# DDR3A.net
KiCad netlist of a schematic drawn in Altium Designer
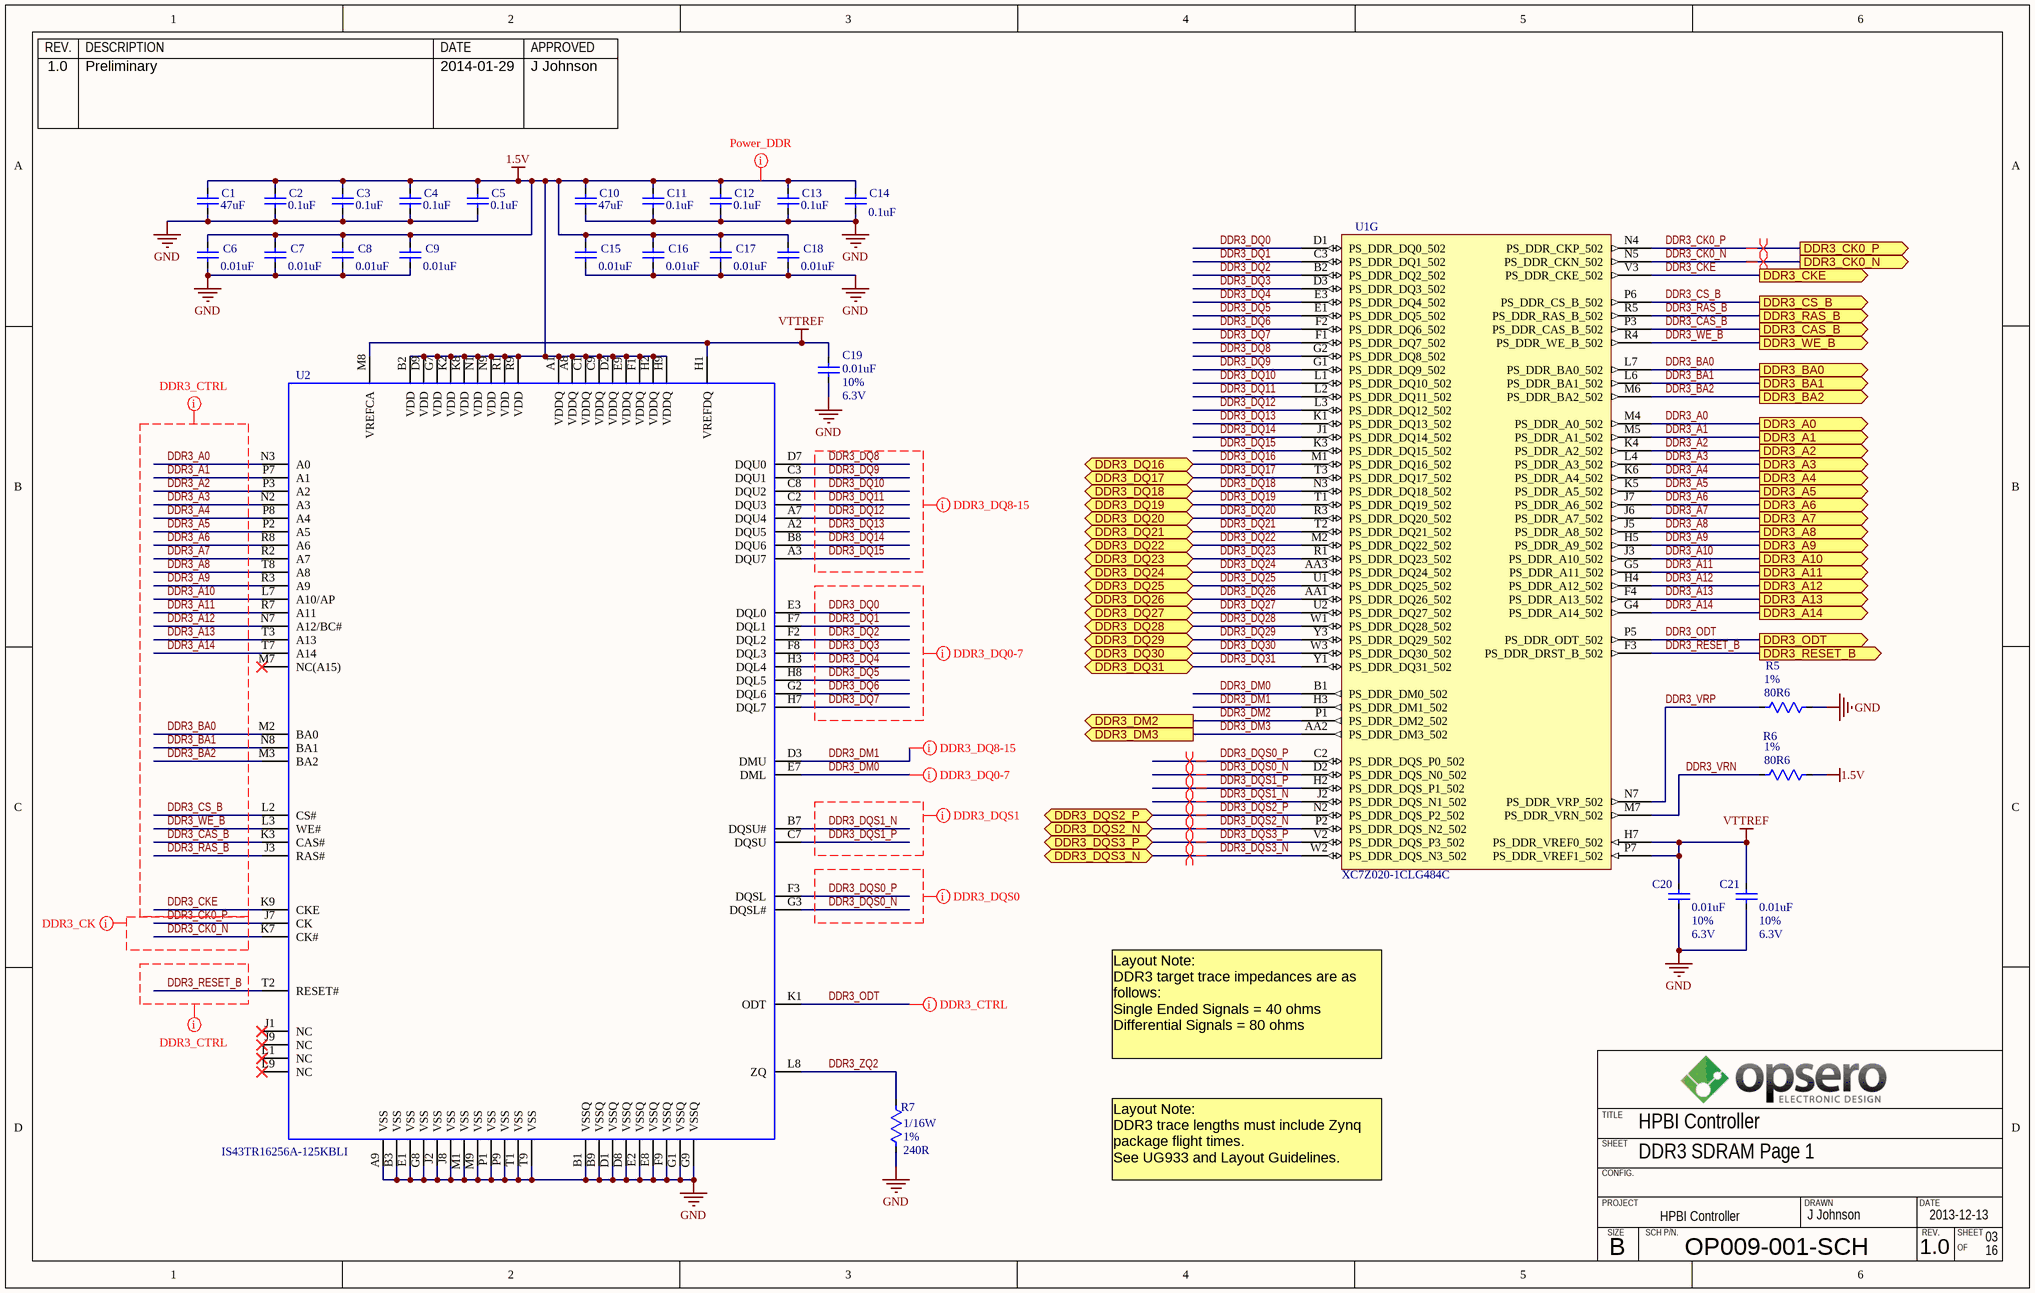
[diagram p0: DDR3A.SchDoc]

(export (version "E")
  (design (tool "Eeschema 10.0.6"))
  (components
    (comp (ref "C1")
      (value "47uF")
      (footprint "CAPC2013X125N")
      (description "Capacitor ceramic, X5R, 47uF, 6.3V, 20%, -55 to +85 C,")
      (fields (field (name "TOLERANCE") "20%") (field (name "VOLTAGE") "6.3V"))
      (libsource (lib "parts") (part "CAPACITOR_NP_TYPE1"))
    )
    (comp (ref "C2")
      (value "0.1uF")
      (footprint "CAPC0603X33N")
      (description "Capacitor ceramic, X5R, 0.1uF, 6.3V, 10%, -55 to +125 C, EIA0201")
      (fields (field (name "TOLERANCE") "10%") (field (name "VOLTAGE") "6.3V"))
      (libsource (lib "parts") (part "CAPACITOR_NP_TYPE1"))
    )
    (comp (ref "C3")
      (value "0.1uF")
      (footprint "CAPC0603X33N")
      (description "Capacitor ceramic, X5R, 0.1uF, 6.3V, 10%, -55 to +125 C, EIA0201")
      (fields (field (name "TOLERANCE") "10%") (field (name "VOLTAGE") "6.3V"))
      (libsource (lib "parts") (part "CAPACITOR_NP_TYPE1"))
    )
    (comp (ref "C4")
      (value "0.1uF")
      (footprint "CAPC0603X33N")
      (description "Capacitor ceramic, X5R, 0.1uF, 6.3V, 10%, -55 to +125 C, EIA0201")
      (fields (field (name "TOLERANCE") "10%") (field (name "VOLTAGE") "6.3V"))
      (libsource (lib "parts") (part "CAPACITOR_NP_TYPE1"))
    )
    (comp (ref "C5")
      (value "0.1uF")
      (footprint "CAPC0603X33N")
      (description "Capacitor ceramic, X5R, 0.1uF, 6.3V, 10%, -55 to +125 C, EIA0201")
      (fields (field (name "TOLERANCE") "10%") (field (name "VOLTAGE") "6.3V"))
      (libsource (lib "parts") (part "CAPACITOR_NP_TYPE1"))
    )
    (comp (ref "C6")
      (value "0.01uF")
      (footprint "CAPC0603X33N")
      (description "Capacitor ceramic, X5R, 0.01uF, 6.3V, 10%, -55 to +125 C, EIA0201")
      (fields (field (name "TOLERANCE") "10%") (field (name "VOLTAGE") "6.3V"))
      (libsource (lib "parts") (part "CAPACITOR_NP_TYPE1"))
    )
    (comp (ref "C7")
      (value "0.01uF")
      (footprint "CAPC0603X33N")
      (description "Capacitor ceramic, X5R, 0.01uF, 6.3V, 10%, -55 to +125 C, EIA0201")
      (fields (field (name "TOLERANCE") "10%") (field (name "VOLTAGE") "6.3V"))
      (libsource (lib "parts") (part "CAPACITOR_NP_TYPE1"))
    )
    (comp (ref "C8")
      (value "0.01uF")
      (footprint "CAPC0603X33N")
      (description "Capacitor ceramic, X5R, 0.01uF, 6.3V, 10%, -55 to +125 C, EIA0201")
      (fields (field (name "TOLERANCE") "10%") (field (name "VOLTAGE") "6.3V"))
      (libsource (lib "parts") (part "CAPACITOR_NP_TYPE1"))
    )
    (comp (ref "C9")
      (value "0.01uF")
      (footprint "CAPC0603X33N")
      (description "Capacitor ceramic, X5R, 0.01uF, 6.3V, 10%, -55 to +125 C, EIA0201")
      (fields (field (name "TOLERANCE") "10%") (field (name "VOLTAGE") "6.3V"))
      (libsource (lib "parts") (part "CAPACITOR_NP_TYPE1"))
    )
    (comp (ref "C10")
      (value "47uF")
      (footprint "CAPC2013X125N")
      (description "Capacitor ceramic, X5R, 47uF, 6.3V, 20%, -55 to +85 C,")
      (fields (field (name "TOLERANCE") "20%") (field (name "VOLTAGE") "6.3V"))
      (libsource (lib "parts") (part "CAPACITOR_NP_TYPE1"))
    )
    (comp (ref "C11")
      (value "0.1uF")
      (footprint "CAPC0603X33N")
      (description "Capacitor ceramic, X5R, 0.1uF, 6.3V, 10%, -55 to +125 C, EIA0201")
      (fields (field (name "TOLERANCE") "10%") (field (name "VOLTAGE") "6.3V"))
      (libsource (lib "parts") (part "CAPACITOR_NP_TYPE1"))
    )
    (comp (ref "C12")
      (value "0.1uF")
      (footprint "CAPC0603X33N")
      (description "Capacitor ceramic, X5R, 0.1uF, 6.3V, 10%, -55 to +125 C, EIA0201")
      (fields (field (name "TOLERANCE") "10%") (field (name "VOLTAGE") "6.3V"))
      (libsource (lib "parts") (part "CAPACITOR_NP_TYPE1"))
    )
    (comp (ref "C13")
      (value "0.1uF")
      (footprint "CAPC0603X33N")
      (description "Capacitor ceramic, X5R, 0.1uF, 6.3V, 10%, -55 to +125 C, EIA0201")
      (fields (field (name "TOLERANCE") "10%") (field (name "VOLTAGE") "6.3V"))
      (libsource (lib "parts") (part "CAPACITOR_NP_TYPE1"))
    )
    (comp (ref "C14")
      (value "0.1uF")
      (footprint "CAPC0603X33N")
      (description "Capacitor ceramic, X5R, 0.1uF, 6.3V, 10%, -55 to +125 C, EIA0201")
      (fields (field (name "TOLERANCE") "10%") (field (name "VOLTAGE") "6.3V"))
      (libsource (lib "parts") (part "CAPACITOR_NP_TYPE1"))
    )
    (comp (ref "C15")
      (value "0.01uF")
      (footprint "CAPC0603X33N")
      (description "Capacitor ceramic, X5R, 0.01uF, 6.3V, 10%, -55 to +125 C, EIA0201")
      (fields (field (name "TOLERANCE") "10%") (field (name "VOLTAGE") "6.3V"))
      (libsource (lib "parts") (part "CAPACITOR_NP_TYPE1"))
    )
    (comp (ref "C16")
      (value "0.01uF")
      (footprint "CAPC0603X33N")
      (description "Capacitor ceramic, X5R, 0.01uF, 6.3V, 10%, -55 to +125 C, EIA0201")
      (fields (field (name "TOLERANCE") "10%") (field (name "VOLTAGE") "6.3V"))
      (libsource (lib "parts") (part "CAPACITOR_NP_TYPE1"))
    )
    (comp (ref "C17")
      (value "0.01uF")
      (footprint "CAPC0603X33N")
      (description "Capacitor ceramic, X5R, 0.01uF, 6.3V, 10%, -55 to +125 C, EIA0201")
      (fields (field (name "TOLERANCE") "10%") (field (name "VOLTAGE") "6.3V"))
      (libsource (lib "parts") (part "CAPACITOR_NP_TYPE1"))
    )
    (comp (ref "C18")
      (value "0.01uF")
      (footprint "CAPC0603X33N")
      (description "Capacitor ceramic, X5R, 0.01uF, 6.3V, 10%, -55 to +125 C, EIA0201")
      (fields (field (name "TOLERANCE") "10%") (field (name "VOLTAGE") "6.3V"))
      (libsource (lib "parts") (part "CAPACITOR_NP_TYPE1"))
    )
    (comp (ref "C19")
      (value "0.01uF")
      (footprint "CAPC0603X33N")
      (description "Capacitor ceramic, X5R, 0.01uF, 6.3V, 10%, -55 to +125 C, EIA0201")
      (fields
        (field (name "TOLERANCE") "10%")
        (field (name "VOLTAGE") "6.3V")
        (field (name "Comment") "CAPACITOR_NP_TYPE1")
      )
      (libsource (lib "parts") (part "CAPACITOR_NP_TYPE1"))
    )
    (comp (ref "C20")
      (value "0.01uF")
      (footprint "CAPC0603X33N")
      (description "Capacitor ceramic, X5R, 0.01uF, 6.3V, 10%, -55 to +125 C, EIA0201")
      (fields
        (field (name "TOLERANCE") "10%")
        (field (name "VOLTAGE") "6.3V")
        (field (name "Comment") "CAPACITOR_NP_TYPE1")
      )
      (libsource (lib "parts") (part "CAPACITOR_NP_TYPE1"))
    )
    (comp (ref "C21")
      (value "0.01uF")
      (footprint "CAPC0603X33N")
      (description "Capacitor ceramic, X5R, 0.01uF, 6.3V, 10%, -55 to +125 C, EIA0201")
      (fields
        (field (name "TOLERANCE") "10%")
        (field (name "VOLTAGE") "6.3V")
        (field (name "Comment") "CAPACITOR_NP_TYPE1")
      )
      (libsource (lib "parts") (part "CAPACITOR_NP_TYPE1"))
    )
    (comp (ref "R5")
      (value "80R6")
      (footprint "RESC1005X33N")
      (description "Resistor, 80R6, 1/16W, 1%, -50 to +155 C, EIA0402, EIA(M)1005")
      (fields (field (name "VOLTAGE") "50V") (field (name "POWER") "1/16W") (field (name "TOLERANCE") "1%"))
      (libsource (lib "parts") (part "RESISTOR_TYPE1"))
    )
    (comp (ref "R6")
      (value "80R6")
      (footprint "RESC1005X33N")
      (description "Resistor, 80R6, 1/16W, 1%, -50 to +155 C, EIA0402, EIA(M)1005")
      (fields (field (name "VOLTAGE") "50V") (field (name "POWER") "1/16W") (field (name "TOLERANCE") "1%"))
      (libsource (lib "parts") (part "RESISTOR_TYPE1"))
    )
    (comp (ref "R7")
      (value "240R")
      (footprint "RESC1005X33N")
      (description "Resistor, 240R, 1/16W, 1%, -50 to +155 C, EIA0402, EIA(M)1005")
      (fields (field (name "VOLTAGE") "50V") (field (name "POWER") "1/16W") (field (name "TOLERANCE") "1%"))
      (libsource (lib "parts") (part "RESISTOR_TYPE1"))
    )
    (comp (ref "U1")
      (value "XC7Z020-1CLG484C")
      (footprint "CLG484")
      (description "667 MHz Zynq™-7000 AP SoC, 130 PS I/O, 200 FPGA I/O, 484-Ball BGA, Speed Grade 1, Commercial Grade")
      (fields (field (name "GENERIC PART NUMBER") "XC7Z020") (field (name "MANUFACTURER") "Xilinx"))
      (libsource (lib "parts") (part "XC7Z020-1CLG484C"))
    )
    (comp (ref "U2")
      (value "IS43TR16256A-125KBLI")
      (footprint "BGA96C80P6X16_900X1300X120")
      (libsource (lib "parts") (part "IS43TR16256A-125KBLI"))
    )
  )
  (nets
    (net (code "1") (name "/DDR3_A0") (class "Default")
      (node (ref "U1") (pin "M4") (pinfunction "PS_DDR_A0_502_M4") (pintype "output"))
      (node (ref "U2") (pin "N3") (pinfunction "A0_N3") (pintype "passive"))
    )
    (net (code "2") (name "/DDR3_A1") (class "Default")
      (node (ref "U1") (pin "M5") (pinfunction "PS_DDR_A1_502_M5") (pintype "output"))
      (node (ref "U2") (pin "P7") (pinfunction "A1_P7") (pintype "passive"))
    )
    (net (code "3") (name "/DDR3_A2") (class "Default")
      (node (ref "U1") (pin "K4") (pinfunction "PS_DDR_A2_502_K4") (pintype "output"))
      (node (ref "U2") (pin "P3") (pinfunction "A2_P3") (pintype "passive"))
    )
    (net (code "4") (name "/DDR3_A3") (class "Default")
      (node (ref "U1") (pin "L4") (pinfunction "PS_DDR_A3_502_L4") (pintype "output"))
      (node (ref "U2") (pin "N2") (pinfunction "A3_N2") (pintype "passive"))
    )
    (net (code "5") (name "/DDR3_A4") (class "Default")
      (node (ref "U1") (pin "K6") (pinfunction "PS_DDR_A4_502_K6") (pintype "output"))
      (node (ref "U2") (pin "P8") (pinfunction "A4_P8") (pintype "passive"))
    )
    (net (code "6") (name "/DDR3_A5") (class "Default")
      (node (ref "U1") (pin "K5") (pinfunction "PS_DDR_A5_502_K5") (pintype "output"))
      (node (ref "U2") (pin "P2") (pinfunction "A5_P2") (pintype "passive"))
    )
    (net (code "7") (name "/DDR3_A6") (class "Default")
      (node (ref "U1") (pin "J7") (pinfunction "PS_DDR_A6_502_J7") (pintype "output"))
      (node (ref "U2") (pin "R8") (pinfunction "A6_R8") (pintype "passive"))
    )
    (net (code "8") (name "/DDR3_A7") (class "Default")
      (node (ref "U1") (pin "J6") (pinfunction "PS_DDR_A7_502_J6") (pintype "output"))
      (node (ref "U2") (pin "R2") (pinfunction "A7_R2") (pintype "passive"))
    )
    (net (code "9") (name "/DDR3_A8") (class "Default")
      (node (ref "U1") (pin "J5") (pinfunction "PS_DDR_A8_502_J5") (pintype "output"))
      (node (ref "U2") (pin "T8") (pinfunction "A8_T8") (pintype "passive"))
    )
    (net (code "10") (name "/DDR3_A9") (class "Default")
      (node (ref "U1") (pin "H5") (pinfunction "PS_DDR_A9_502_H5") (pintype "output"))
      (node (ref "U2") (pin "R3") (pinfunction "A9_R3") (pintype "passive"))
    )
    (net (code "11") (name "/DDR3_A10") (class "Default")
      (node (ref "U1") (pin "J3") (pinfunction "PS_DDR_A10_502_J3") (pintype "output"))
      (node (ref "U2") (pin "L7") (pinfunction "A10/AP_L7") (pintype "passive"))
    )
    (net (code "12") (name "/DDR3_A11") (class "Default")
      (node (ref "U1") (pin "G5") (pinfunction "PS_DDR_A11_502_G5") (pintype "output"))
      (node (ref "U2") (pin "R7") (pinfunction "A11_R7") (pintype "passive"))
    )
    (net (code "13") (name "/DDR3_A12") (class "Default")
      (node (ref "U1") (pin "H4") (pinfunction "PS_DDR_A12_502_H4") (pintype "output"))
      (node (ref "U2") (pin "N7") (pinfunction "A12/BC#_N7") (pintype "passive"))
    )
    (net (code "14") (name "/DDR3_A13") (class "Default")
      (node (ref "U1") (pin "F4") (pinfunction "PS_DDR_A13_502_F4") (pintype "output"))
      (node (ref "U2") (pin "T3") (pinfunction "A13_T3") (pintype "passive"))
    )
    (net (code "15") (name "/DDR3_A14") (class "Default")
      (node (ref "U1") (pin "G4") (pinfunction "PS_DDR_A14_502_G4") (pintype "output"))
      (node (ref "U2") (pin "T7") (pinfunction "A14_T7") (pintype "passive"))
    )
    (net (code "16") (name "/DDR3_BA0") (class "Default")
      (node (ref "U1") (pin "L7") (pinfunction "PS_DDR_BA0_502_L7") (pintype "output"))
      (node (ref "U2") (pin "M2") (pinfunction "BA0_M2") (pintype "passive"))
    )
    (net (code "17") (name "/DDR3_BA1") (class "Default")
      (node (ref "U1") (pin "L6") (pinfunction "PS_DDR_BA1_502_L6") (pintype "output"))
      (node (ref "U2") (pin "N8") (pinfunction "BA1_N8") (pintype "passive"))
    )
    (net (code "18") (name "/DDR3_BA2") (class "Default")
      (node (ref "U1") (pin "M6") (pinfunction "PS_DDR_BA2_502_M6") (pintype "output"))
      (node (ref "U2") (pin "M3") (pinfunction "BA2_M3") (pintype "passive"))
    )
    (net (code "19") (name "/DDR3_CAS_B") (class "Default")
      (node (ref "U1") (pin "P3") (pinfunction "PS_DDR_CAS_B_502_P3") (pintype "output"))
      (node (ref "U2") (pin "K3") (pinfunction "CAS#_K3") (pintype "passive"))
    )
    (net (code "20") (name "/DDR3_CK0_N") (class "Default")
      (node (ref "U1") (pin "N5") (pinfunction "PS_DDR_CKN_502_N5") (pintype "output"))
      (node (ref "U2") (pin "K7") (pinfunction "CK#_K7") (pintype "passive"))
    )
    (net (code "21") (name "/DDR3_CK0_P") (class "Default")
      (node (ref "U1") (pin "N4") (pinfunction "PS_DDR_CKP_502_N4") (pintype "output"))
      (node (ref "U2") (pin "J7") (pinfunction "CK_J7") (pintype "passive"))
    )
    (net (code "22") (name "/DDR3_CKE") (class "Default")
      (node (ref "U1") (pin "V3") (pinfunction "PS_DDR_CKE_502_V3") (pintype "output"))
      (node (ref "U2") (pin "K9") (pinfunction "CKE_K9") (pintype "passive"))
    )
    (net (code "23") (name "/DDR3_CS_B") (class "Default")
      (node (ref "U1") (pin "P6") (pinfunction "PS_DDR_CS_B_502_P6") (pintype "output"))
      (node (ref "U2") (pin "L2") (pinfunction "CS#_L2") (pintype "passive"))
    )
    (net (code "24") (name "/DDR3_DM0") (class "Default")
      (node (ref "U1") (pin "B1") (pinfunction "PS_DDR_DM0_502_B1") (pintype "output"))
      (node (ref "U2") (pin "E7") (pinfunction "DML_E7") (pintype "passive"))
    )
    (net (code "25") (name "/DDR3_DM1") (class "Default")
      (node (ref "U1") (pin "H3") (pinfunction "PS_DDR_DM1_502_H3") (pintype "output"))
      (node (ref "U2") (pin "D3") (pinfunction "DMU_D3") (pintype "passive"))
    )
    (net (code "26") (name "/DDR3_DM2") (class "Default")
      (node (ref "U1") (pin "P1") (pinfunction "PS_DDR_DM2_502_P1") (pintype "output"))
    )
    (net (code "27") (name "/DDR3_DM3") (class "Default")
      (node (ref "U1") (pin "AA2") (pinfunction "PS_DDR_DM3_502_AA2") (pintype "output"))
    )
    (net (code "28") (name "/DDR3_DQ0") (class "Default")
      (node (ref "U1") (pin "D1") (pinfunction "PS_DDR_DQ0_502_D1") (pintype "bidirectional"))
      (node (ref "U2") (pin "E3") (pinfunction "DQL0_E3") (pintype "passive"))
    )
    (net (code "29") (name "/DDR3_DQ1") (class "Default")
      (node (ref "U1") (pin "C3") (pinfunction "PS_DDR_DQ1_502_C3") (pintype "bidirectional"))
      (node (ref "U2") (pin "F7") (pinfunction "DQL1_F7") (pintype "passive"))
    )
    (net (code "30") (name "/DDR3_DQ2") (class "Default")
      (node (ref "U1") (pin "B2") (pinfunction "PS_DDR_DQ2_502_B2") (pintype "bidirectional"))
      (node (ref "U2") (pin "F2") (pinfunction "DQL2_F2") (pintype "passive"))
    )
    (net (code "31") (name "/DDR3_DQ3") (class "Default")
      (node (ref "U1") (pin "D3") (pinfunction "PS_DDR_DQ3_502_D3") (pintype "bidirectional"))
      (node (ref "U2") (pin "F8") (pinfunction "DQL3_F8") (pintype "passive"))
    )
    (net (code "32") (name "/DDR3_DQ4") (class "Default")
      (node (ref "U1") (pin "E3") (pinfunction "PS_DDR_DQ4_502_E3") (pintype "bidirectional"))
      (node (ref "U2") (pin "H3") (pinfunction "DQL4_H3") (pintype "passive"))
    )
    (net (code "33") (name "/DDR3_DQ5") (class "Default")
      (node (ref "U1") (pin "E1") (pinfunction "PS_DDR_DQ5_502_E1") (pintype "bidirectional"))
      (node (ref "U2") (pin "H8") (pinfunction "DQL5_H8") (pintype "passive"))
    )
    (net (code "34") (name "/DDR3_DQ6") (class "Default")
      (node (ref "U1") (pin "F2") (pinfunction "PS_DDR_DQ6_502_F2") (pintype "bidirectional"))
      (node (ref "U2") (pin "G2") (pinfunction "DQL6_G2") (pintype "passive"))
    )
    (net (code "35") (name "/DDR3_DQ7") (class "Default")
      (node (ref "U1") (pin "F1") (pinfunction "PS_DDR_DQ7_502_F1") (pintype "bidirectional"))
      (node (ref "U2") (pin "H7") (pinfunction "DQL7_H7") (pintype "passive"))
    )
    (net (code "36") (name "/DDR3_DQ8") (class "Default")
      (node (ref "U1") (pin "G2") (pinfunction "PS_DDR_DQ8_502_G2") (pintype "bidirectional"))
      (node (ref "U2") (pin "D7") (pinfunction "DQU0_D7") (pintype "passive"))
    )
    (net (code "37") (name "/DDR3_DQ9") (class "Default")
      (node (ref "U1") (pin "G1") (pinfunction "PS_DDR_DQ9_502_G1") (pintype "bidirectional"))
      (node (ref "U2") (pin "C3") (pinfunction "DQU1_C3") (pintype "passive"))
    )
    (net (code "38") (name "/DDR3_DQ10") (class "Default")
      (node (ref "U1") (pin "L1") (pinfunction "PS_DDR_DQ10_502_L1") (pintype "bidirectional"))
      (node (ref "U2") (pin "C8") (pinfunction "DQU2_C8") (pintype "passive"))
    )
    (net (code "39") (name "/DDR3_DQ11") (class "Default")
      (node (ref "U1") (pin "L2") (pinfunction "PS_DDR_DQ11_502_L2") (pintype "bidirectional"))
      (node (ref "U2") (pin "C2") (pinfunction "DQU3_C2") (pintype "passive"))
    )
    (net (code "40") (name "/DDR3_DQ12") (class "Default")
      (node (ref "U1") (pin "L3") (pinfunction "PS_DDR_DQ12_502_L3") (pintype "bidirectional"))
      (node (ref "U2") (pin "A7") (pinfunction "DQU4_A7") (pintype "passive"))
    )
    (net (code "41") (name "/DDR3_DQ13") (class "Default")
      (node (ref "U1") (pin "K1") (pinfunction "PS_DDR_DQ13_502_K1") (pintype "bidirectional"))
      (node (ref "U2") (pin "A2") (pinfunction "DQU5_A2") (pintype "passive"))
    )
    (net (code "42") (name "/DDR3_DQ14") (class "Default")
      (node (ref "U1") (pin "J1") (pinfunction "PS_DDR_DQ14_502_J1") (pintype "bidirectional"))
      (node (ref "U2") (pin "B8") (pinfunction "DQU6_B8") (pintype "passive"))
    )
    (net (code "43") (name "/DDR3_DQ15") (class "Default")
      (node (ref "U1") (pin "K3") (pinfunction "PS_DDR_DQ15_502_K3") (pintype "bidirectional"))
      (node (ref "U2") (pin "A3") (pinfunction "DQU7_A3") (pintype "passive"))
    )
    (net (code "44") (name "/DDR3_DQ16") (class "Default")
      (node (ref "U1") (pin "M1") (pinfunction "PS_DDR_DQ16_502_M1") (pintype "bidirectional"))
    )
    (net (code "45") (name "/DDR3_DQ17") (class "Default")
      (node (ref "U1") (pin "T3") (pinfunction "PS_DDR_DQ17_502_T3") (pintype "bidirectional"))
    )
    (net (code "46") (name "/DDR3_DQ18") (class "Default")
      (node (ref "U1") (pin "N3") (pinfunction "PS_DDR_DQ18_502_N3") (pintype "bidirectional"))
    )
    (net (code "47") (name "/DDR3_DQ19") (class "Default")
      (node (ref "U1") (pin "T1") (pinfunction "PS_DDR_DQ19_502_T1") (pintype "bidirectional"))
    )
    (net (code "48") (name "/DDR3_DQ20") (class "Default")
      (node (ref "U1") (pin "R3") (pinfunction "PS_DDR_DQ20_502_R3") (pintype "bidirectional"))
    )
    (net (code "49") (name "/DDR3_DQ21") (class "Default")
      (node (ref "U1") (pin "T2") (pinfunction "PS_DDR_DQ21_502_T2") (pintype "bidirectional"))
    )
    (net (code "50") (name "/DDR3_DQ22") (class "Default")
      (node (ref "U1") (pin "M2") (pinfunction "PS_DDR_DQ22_502_M2") (pintype "bidirectional"))
    )
    (net (code "51") (name "/DDR3_DQ23") (class "Default")
      (node (ref "U1") (pin "R1") (pinfunction "PS_DDR_DQ23_502_R1") (pintype "bidirectional"))
    )
    (net (code "52") (name "/DDR3_DQ24") (class "Default")
      (node (ref "U1") (pin "AA3") (pinfunction "PS_DDR_DQ24_502_AA3") (pintype "bidirectional"))
    )
    (net (code "53") (name "/DDR3_DQ25") (class "Default")
      (node (ref "U1") (pin "U1") (pinfunction "PS_DDR_DQ25_502_U1") (pintype "bidirectional"))
    )
    (net (code "54") (name "/DDR3_DQ26") (class "Default")
      (node (ref "U1") (pin "AA1") (pinfunction "PS_DDR_DQ26_502_AA1") (pintype "bidirectional"))
    )
    (net (code "55") (name "/DDR3_DQ27") (class "Default")
      (node (ref "U1") (pin "U2") (pinfunction "PS_DDR_DQ27_502_U2") (pintype "bidirectional"))
    )
    (net (code "56") (name "/DDR3_DQ28") (class "Default")
      (node (ref "U1") (pin "W1") (pinfunction "PS_DDR_DQ28_502_W1") (pintype "bidirectional"))
    )
    (net (code "57") (name "/DDR3_DQ29") (class "Default")
      (node (ref "U1") (pin "Y3") (pinfunction "PS_DDR_DQ29_502_Y3") (pintype "bidirectional"))
    )
    (net (code "58") (name "/DDR3_DQ30") (class "Default")
      (node (ref "U1") (pin "W3") (pinfunction "PS_DDR_DQ30_502_W3") (pintype "bidirectional"))
    )
    (net (code "59") (name "/DDR3_DQ31") (class "Default")
      (node (ref "U1") (pin "Y1") (pinfunction "PS_DDR_DQ31_502_Y1") (pintype "bidirectional"))
    )
    (net (code "60") (name "/DDR3_DQS0_N") (class "Default")
      (node (ref "U1") (pin "D2") (pinfunction "PS_DDR_DQS_N0_502_D2") (pintype "bidirectional"))
      (node (ref "U2") (pin "G3") (pinfunction "DQSL#_G3") (pintype "passive"))
    )
    (net (code "61") (name "/DDR3_DQS0_P") (class "Default")
      (node (ref "U1") (pin "C2") (pinfunction "PS_DDR_DQS_P0_502_C2") (pintype "bidirectional"))
      (node (ref "U2") (pin "F3") (pinfunction "DQSL_F3") (pintype "passive"))
    )
    (net (code "62") (name "/DDR3_DQS1_N") (class "Default")
      (node (ref "U1") (pin "J2") (pinfunction "PS_DDR_DQS_N1_502_J2") (pintype "bidirectional"))
      (node (ref "U2") (pin "B7") (pinfunction "DQSU#_B7") (pintype "passive"))
    )
    (net (code "63") (name "/DDR3_DQS1_P") (class "Default")
      (node (ref "U1") (pin "H2") (pinfunction "PS_DDR_DQS_P1_502_H2") (pintype "bidirectional"))
      (node (ref "U2") (pin "C7") (pinfunction "DQSU_C7") (pintype "passive"))
    )
    (net (code "64") (name "/DDR3_DQS2_N") (class "Default")
      (node (ref "U1") (pin "P2") (pinfunction "PS_DDR_DQS_N2_502_P2") (pintype "bidirectional"))
    )
    (net (code "65") (name "/DDR3_DQS2_P") (class "Default")
      (node (ref "U1") (pin "N2") (pinfunction "PS_DDR_DQS_P2_502_N2") (pintype "bidirectional"))
    )
    (net (code "66") (name "/DDR3_DQS3_N") (class "Default")
      (node (ref "U1") (pin "W2") (pinfunction "PS_DDR_DQS_N3_502_W2") (pintype "bidirectional"))
    )
    (net (code "67") (name "/DDR3_DQS3_P") (class "Default")
      (node (ref "U1") (pin "V2") (pinfunction "PS_DDR_DQS_P3_502_V2") (pintype "bidirectional"))
    )
    (net (code "68") (name "/DDR3_ODT") (class "Default")
      (node (ref "U1") (pin "P5") (pinfunction "PS_DDR_ODT_502_P5") (pintype "output"))
      (node (ref "U2") (pin "K1") (pinfunction "ODT_K1") (pintype "passive"))
    )
    (net (code "69") (name "/DDR3_RAS_B") (class "Default")
      (node (ref "U1") (pin "R5") (pinfunction "PS_DDR_RAS_B_502_R5") (pintype "output"))
      (node (ref "U2") (pin "J3") (pinfunction "RAS#_J3") (pintype "passive"))
    )
    (net (code "70") (name "/DDR3_RESET_B") (class "Default")
      (node (ref "U1") (pin "F3") (pinfunction "PS_DDR_DRST_B_502_F3") (pintype "output"))
      (node (ref "U2") (pin "T2") (pinfunction "RESET#_T2") (pintype "passive"))
    )
    (net (code "71") (name "/DDR3_VRN") (class "Default")
      (node (ref "R6") (pin "2") (pinfunction "2_2") (pintype "passive"))
      (node (ref "U1") (pin "M7") (pinfunction "PS_DDR_VRN_502_M7") (pintype "output"))
    )
    (net (code "72") (name "/DDR3_VRP") (class "Default")
      (node (ref "R5") (pin "1") (pinfunction "1_1") (pintype "passive"))
      (node (ref "U1") (pin "N7") (pinfunction "PS_DDR_VRP_502_N7") (pintype "output"))
    )
    (net (code "73") (name "/DDR3_WE_B") (class "Default")
      (node (ref "U1") (pin "R4") (pinfunction "PS_DDR_WE_B_502_R4") (pintype "output"))
      (node (ref "U2") (pin "L3") (pinfunction "WE#_L3") (pintype "passive"))
    )
    (net (code "74") (name "/DDR3_ZQ2") (class "Default")
      (node (ref "R7") (pin "2") (pinfunction "2_2") (pintype "passive"))
      (node (ref "U2") (pin "L8") (pinfunction "ZQ_L8") (pintype "passive"))
    )
    (net (code "75") (name "1.5V") (class "Default")
      (node (ref "C1") (pin "1") (pinfunction "1_1") (pintype "passive"))
      (node (ref "C10") (pin "1") (pinfunction "1_1") (pintype "passive"))
      (node (ref "C11") (pin "1") (pinfunction "1_1") (pintype "passive"))
      (node (ref "C12") (pin "1") (pinfunction "1_1") (pintype "passive"))
      (node (ref "C13") (pin "1") (pinfunction "1_1") (pintype "passive"))
      (node (ref "C14") (pin "1") (pinfunction "1_1") (pintype "passive"))
      (node (ref "C15") (pin "1") (pinfunction "1_1") (pintype "passive"))
      (node (ref "C16") (pin "1") (pinfunction "1_1") (pintype "passive"))
      (node (ref "C17") (pin "1") (pinfunction "1_1") (pintype "passive"))
      (node (ref "C18") (pin "1") (pinfunction "1_1") (pintype "passive"))
      (node (ref "C2") (pin "1") (pinfunction "1_1") (pintype "passive"))
      (node (ref "C3") (pin "1") (pinfunction "1_1") (pintype "passive"))
      (node (ref "C4") (pin "1") (pinfunction "1_1") (pintype "passive"))
      (node (ref "C5") (pin "1") (pinfunction "1_1") (pintype "passive"))
      (node (ref "C6") (pin "1") (pinfunction "1_1") (pintype "passive"))
      (node (ref "C7") (pin "1") (pinfunction "1_1") (pintype "passive"))
      (node (ref "C8") (pin "1") (pinfunction "1_1") (pintype "passive"))
      (node (ref "C9") (pin "1") (pinfunction "1_1") (pintype "passive"))
      (node (ref "R6") (pin "1") (pinfunction "1_1") (pintype "passive"))
      (node (ref "U2") (pin "A1") (pinfunction "VDDQ_A1") (pintype "passive"))
      (node (ref "U2") (pin "A8") (pinfunction "VDDQ_A8") (pintype "passive"))
      (node (ref "U2") (pin "B2") (pinfunction "VDD_B2") (pintype "passive"))
      (node (ref "U2") (pin "C1") (pinfunction "VDDQ_C1") (pintype "passive"))
      (node (ref "U2") (pin "C9") (pinfunction "VDDQ_C9") (pintype "passive"))
      (node (ref "U2") (pin "D2") (pinfunction "VDDQ_D2") (pintype "passive"))
      (node (ref "U2") (pin "D9") (pinfunction "VDD_D9") (pintype "passive"))
      (node (ref "U2") (pin "E9") (pinfunction "VDDQ_E9") (pintype "passive"))
      (node (ref "U2") (pin "F1") (pinfunction "VDDQ_F1") (pintype "passive"))
      (node (ref "U2") (pin "G7") (pinfunction "VDD_G7") (pintype "passive"))
      (node (ref "U2") (pin "H2") (pinfunction "VDDQ_H2") (pintype "passive"))
      (node (ref "U2") (pin "H9") (pinfunction "VDDQ_H9") (pintype "passive"))
      (node (ref "U2") (pin "K2") (pinfunction "VDD_K2") (pintype "passive"))
      (node (ref "U2") (pin "K8") (pinfunction "VDD_K8") (pintype "passive"))
      (node (ref "U2") (pin "N1") (pinfunction "VDD_N1") (pintype "passive"))
      (node (ref "U2") (pin "N9") (pinfunction "VDD_N9") (pintype "passive"))
      (node (ref "U2") (pin "R1") (pinfunction "VDD_R1") (pintype "passive"))
      (node (ref "U2") (pin "R9") (pinfunction "VDD_R9") (pintype "passive"))
    )
    (net (code "76") (name "GND") (class "Default")
      (node (ref "C1") (pin "2") (pinfunction "2_2") (pintype "passive"))
      (node (ref "C10") (pin "2") (pinfunction "2_2") (pintype "passive"))
      (node (ref "C11") (pin "2") (pinfunction "2_2") (pintype "passive"))
      (node (ref "C12") (pin "2") (pinfunction "2_2") (pintype "passive"))
      (node (ref "C13") (pin "2") (pinfunction "2_2") (pintype "passive"))
      (node (ref "C14") (pin "2") (pinfunction "2_2") (pintype "passive"))
      (node (ref "C15") (pin "2") (pinfunction "2_2") (pintype "passive"))
      (node (ref "C16") (pin "2") (pinfunction "2_2") (pintype "passive"))
      (node (ref "C17") (pin "2") (pinfunction "2_2") (pintype "passive"))
      (node (ref "C18") (pin "2") (pinfunction "2_2") (pintype "passive"))
      (node (ref "C19") (pin "2") (pinfunction "2_2") (pintype "passive"))
      (node (ref "C2") (pin "2") (pinfunction "2_2") (pintype "passive"))
      (node (ref "C20") (pin "2") (pinfunction "2_2") (pintype "passive"))
      (node (ref "C21") (pin "2") (pinfunction "2_2") (pintype "passive"))
      (node (ref "C3") (pin "2") (pinfunction "2_2") (pintype "passive"))
      (node (ref "C4") (pin "2") (pinfunction "2_2") (pintype "passive"))
      (node (ref "C5") (pin "2") (pinfunction "2_2") (pintype "passive"))
      (node (ref "C6") (pin "2") (pinfunction "2_2") (pintype "passive"))
      (node (ref "C7") (pin "2") (pinfunction "2_2") (pintype "passive"))
      (node (ref "C8") (pin "2") (pinfunction "2_2") (pintype "passive"))
      (node (ref "C9") (pin "2") (pinfunction "2_2") (pintype "passive"))
      (node (ref "R5") (pin "2") (pinfunction "2_2") (pintype "passive"))
      (node (ref "R7") (pin "1") (pinfunction "1_1") (pintype "passive"))
      (node (ref "U2") (pin "A9") (pinfunction "VSS_A9") (pintype "passive"))
      (node (ref "U2") (pin "B1") (pinfunction "VSSQ_B1") (pintype "passive"))
      (node (ref "U2") (pin "B3") (pinfunction "VSS_B3") (pintype "passive"))
      (node (ref "U2") (pin "B9") (pinfunction "VSSQ_B9") (pintype "passive"))
      (node (ref "U2") (pin "D1") (pinfunction "VSSQ_D1") (pintype "passive"))
      (node (ref "U2") (pin "D8") (pinfunction "VSSQ_D8") (pintype "passive"))
      (node (ref "U2") (pin "E1") (pinfunction "VSS_E1") (pintype "passive"))
      (node (ref "U2") (pin "E2") (pinfunction "VSSQ_E2") (pintype "passive"))
      (node (ref "U2") (pin "E8") (pinfunction "VSSQ_E8") (pintype "passive"))
      (node (ref "U2") (pin "F9") (pinfunction "VSSQ_F9") (pintype "passive"))
      (node (ref "U2") (pin "G1") (pinfunction "VSSQ_G1") (pintype "passive"))
      (node (ref "U2") (pin "G8") (pinfunction "VSS_G8") (pintype "passive"))
      (node (ref "U2") (pin "G9") (pinfunction "VSSQ_G9") (pintype "passive"))
      (node (ref "U2") (pin "J2") (pinfunction "VSS_J2") (pintype "passive"))
      (node (ref "U2") (pin "J8") (pinfunction "VSS_J8") (pintype "passive"))
      (node (ref "U2") (pin "M1") (pinfunction "VSS_M1") (pintype "passive"))
      (node (ref "U2") (pin "M9") (pinfunction "VSS_M9") (pintype "passive"))
      (node (ref "U2") (pin "P1") (pinfunction "VSS_P1") (pintype "passive"))
      (node (ref "U2") (pin "P9") (pinfunction "VSS_P9") (pintype "passive"))
      (node (ref "U2") (pin "T1") (pinfunction "VSS_T1") (pintype "passive"))
      (node (ref "U2") (pin "T9") (pinfunction "VSS_T9") (pintype "passive"))
    )
    (net (code "77") (name "VTTREF") (class "Default")
      (node (ref "C19") (pin "1") (pinfunction "1_1") (pintype "passive"))
      (node (ref "C20") (pin "1") (pinfunction "1_1") (pintype "passive"))
      (node (ref "C21") (pin "1") (pinfunction "1_1") (pintype "passive"))
      (node (ref "U1") (pin "H7") (pinfunction "PS_DDR_VREF0_502_H7") (pintype "input"))
      (node (ref "U1") (pin "P7") (pinfunction "PS_DDR_VREF1_502_P7") (pintype "input"))
      (node (ref "U2") (pin "H1") (pinfunction "VREFDQ_H1") (pintype "passive"))
      (node (ref "U2") (pin "M8") (pinfunction "VREFCA_M8") (pintype "passive"))
    )
    (net (code "78") (name "unconnected-(U2-NC(A15)-PadM7)") (class "Default")
      (node (ref "U2") (pin "M7") (pinfunction "NC(A15)_M7") (pintype "passive+no_connect"))
    )
    (net (code "79") (name "unconnected-(U2-NC-PadJ1)") (class "Default")
      (node (ref "U2") (pin "J1") (pinfunction "NC_J1") (pintype "passive+no_connect"))
    )
    (net (code "80") (name "unconnected-(U2-NC-PadJ9)") (class "Default")
      (node (ref "U2") (pin "J9") (pinfunction "NC_J9") (pintype "passive+no_connect"))
    )
    (net (code "81") (name "unconnected-(U2-NC-PadL1)") (class "Default")
      (node (ref "U2") (pin "L1") (pinfunction "NC_L1") (pintype "passive+no_connect"))
    )
    (net (code "82") (name "unconnected-(U2-NC-PadL9)") (class "Default")
      (node (ref "U2") (pin "L9") (pinfunction "NC_L9") (pintype "passive+no_connect"))
    )
  )
)
